# lab2_samarin_boost.net
KiCad netlist of a schematic drawn in Altium Designer
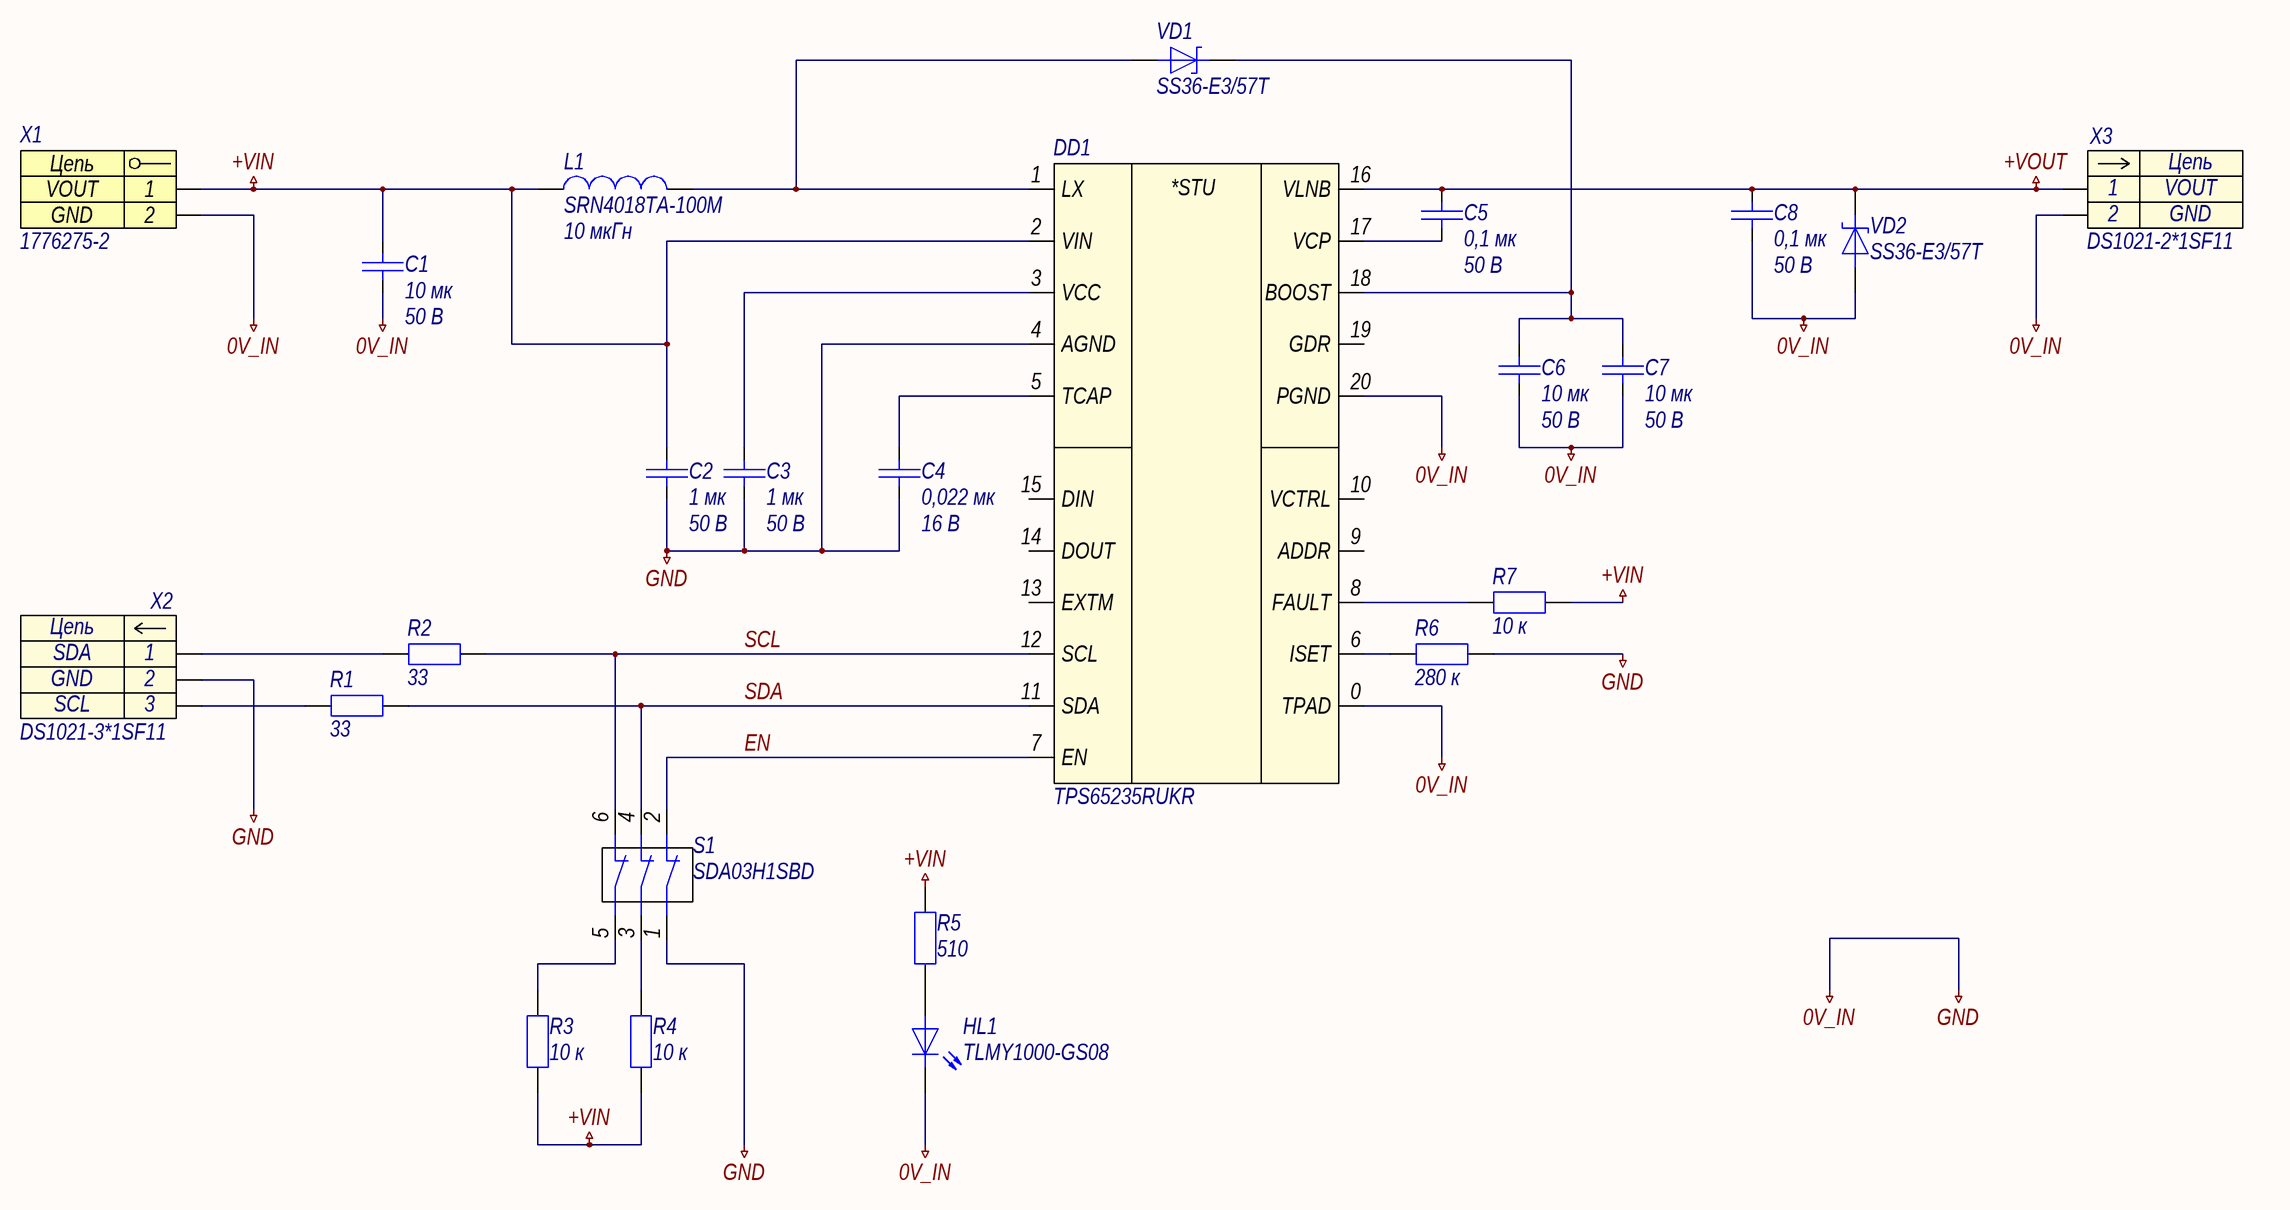
[diagram p0: lab2_samarin_boost.SchDoc]

(export (version "E")
  (design (tool "Eeschema 10.0.6"))
  (components
    (comp (ref "C1")
      (value "10 мк")
      (footprint "C1206")
      (description "=Описание")
      (fields (field (name "НАПРЯЖЕНИЕ") "50 В"))
      (libsource (lib "Database_Students") (part "C-NONPOLAR"))
    )
    (comp (ref "C2")
      (value "1 мк")
      (footprint "C0603")
      (description "=Описание")
      (fields (field (name "НАПРЯЖЕНИЕ") "50 В"))
      (libsource (lib "Database_Students") (part "C-NONPOLAR"))
    )
    (comp (ref "C3")
      (value "1 мк")
      (footprint "C0603")
      (description "=Описание")
      (fields (field (name "НАПРЯЖЕНИЕ") "50 В"))
      (libsource (lib "Database_Students") (part "C-NONPOLAR"))
    )
    (comp (ref "C4")
      (value "0,022 мк")
      (footprint "C0201")
      (description "=Описание")
      (fields (field (name "НАПРЯЖЕНИЕ") "16 В"))
      (libsource (lib "Database_Students") (part "C-NONPOLAR"))
    )
    (comp (ref "C5")
      (value "0,1 мк")
      (footprint "C0603")
      (description "=Описание")
      (fields (field (name "НАПРЯЖЕНИЕ") "50 В"))
      (libsource (lib "Database_Students") (part "C-NONPOLAR"))
    )
    (comp (ref "C6")
      (value "10 мк")
      (footprint "C1206")
      (description "=Описание")
      (fields (field (name "НАПРЯЖЕНИЕ") "50 В"))
      (libsource (lib "Database_Students") (part "C-NONPOLAR"))
    )
    (comp (ref "C7")
      (value "10 мк")
      (footprint "C1206")
      (description "=Описание")
      (fields (field (name "НАПРЯЖЕНИЕ") "50 В"))
      (libsource (lib "Database_Students") (part "C-NONPOLAR"))
    )
    (comp (ref "C8")
      (value "0,1 мк")
      (footprint "C0603")
      (description "=Описание")
      (fields (field (name "НАПРЯЖЕНИЕ") "50 В"))
      (libsource (lib "Database_Students") (part "C-NONPOLAR"))
    )
    (comp (ref "DD1")
      (value "TPS65235RUKR")
      (footprint "QFN-20")
      (description "=Описание")
      (libsource (lib "Database_Students") (part "TPS65235RUKR"))
    )
    (comp (ref "HL1")
      (value "TLMY1000-GS08")
      (footprint "HL0603")
      (description "=Описание")
      (libsource (lib "Database_Students") (part "HL-COMMON"))
    )
    (comp (ref "L1")
      (value "SRN4018TA-100M")
      (footprint "SRN-2-400X400X180")
      (description "=Описание")
      (fields (field (name "ИНДУКТИВНОСТЬ") "10 мкГн"))
      (libsource (lib "Database_Students") (part "INDUCTOR-COMMON"))
    )
    (comp (ref "R1")
      (value "33")
      (footprint "R0603")
      (description "=Описание")
      (libsource (lib "Database_Students") (part "R-COMMON"))
    )
    (comp (ref "R2")
      (value "33")
      (footprint "R0603")
      (description "=Описание")
      (libsource (lib "Database_Students") (part "R-COMMON"))
    )
    (comp (ref "R3")
      (value "10 к")
      (footprint "R0603")
      (description "=Описание")
      (libsource (lib "Database_Students") (part "R-COMMON"))
    )
    (comp (ref "R4")
      (value "10 к")
      (footprint "R0603")
      (description "=Описание")
      (libsource (lib "Database_Students") (part "R-COMMON"))
    )
    (comp (ref "R5")
      (value "510")
      (footprint "R0603")
      (description "=Описание")
      (libsource (lib "Database_Students") (part "R-COMMON"))
    )
    (comp (ref "R6")
      (value "280 к")
      (footprint "R0603")
      (description "=Описание")
      (libsource (lib "Database_Students") (part "R-COMMON"))
    )
    (comp (ref "R7")
      (value "10 к")
      (footprint "R0603")
      (description "=Описание")
      (libsource (lib "Database_Students") (part "R-COMMON"))
    )
    (comp (ref "S1")
      (value "SDA03H1SBD")
      (footprint "DIP-SWITCH-03")
      (description "=Описание")
      (libsource (lib "Database_Students") (part "SWITCH-03"))
    )
    (comp (ref "VD1")
      (value "SS36-E3/57T")
      (footprint "DO-214AB")
      (description "=Описание")
      (libsource (lib "Database_Students") (part "DIODE-SCHOTTKY"))
    )
    (comp (ref "VD2")
      (value "SS36-E3/57T")
      (footprint "DO-214AB")
      (description "=Описание")
      (libsource (lib "Database_Students") (part "DIODE-SCHOTTKY"))
    )
    (comp (ref "X1")
      (value "1776275-2")
      (footprint "1776275-2")
      (description "=Описание")
      (libsource (lib "Database_Students") (part "HEADER-2-TRM"))
    )
    (comp (ref "X2")
      (value "DS1021-3*1SF11")
      (footprint "pls-2,54-3-tht-v:pls-2,54-3")
      (libsource (lib "header-3_plg") (part "HEADER-3_PLG"))
    )
    (comp (ref "X3")
      (value "DS1021-2*1SF11")
      (footprint "pls-2,54-2-tht-v:pls-2,54")
      (libsource (lib "header-2_plg") (part "HEADER-2_PLG"))
    )
  )
  (nets
    (net (code "1") (name "+VIN") (class "Default")
      (node (ref "C1") (pin "1") (pinfunction "1_1") (pintype "passive"))
      (node (ref "C2") (pin "1") (pinfunction "1_1") (pintype "passive"))
      (node (ref "DD1") (pin "2") (pinfunction "VIN_2") (pintype "passive"))
      (node (ref "L1") (pin "1") (pinfunction "1_1") (pintype "passive"))
      (node (ref "R3") (pin "1") (pinfunction "1_1") (pintype "passive"))
      (node (ref "R4") (pin "1") (pinfunction "1_1") (pintype "passive"))
      (node (ref "R5") (pin "2") (pinfunction "2_2") (pintype "passive"))
      (node (ref "R7") (pin "2") (pinfunction "2_2") (pintype "passive"))
      (node (ref "X1") (pin "1") (pinfunction "1_1") (pintype "passive"))
    )
    (net (code "2") (name "+VOUT") (class "Default")
      (node (ref "C5") (pin "1") (pinfunction "1_1") (pintype "passive"))
      (node (ref "C8") (pin "1") (pinfunction "1_1") (pintype "passive"))
      (node (ref "DD1") (pin "16") (pinfunction "VLNB_16") (pintype "passive"))
      (node (ref "VD2") (pin "1") (pinfunction "1_1") (pintype "passive"))
      (node (ref "X3") (pin "1") (pinfunction "1_1") (pintype "passive"))
    )
    (net (code "3") (name "/EN") (class "Default")
      (node (ref "DD1") (pin "7") (pinfunction "EN_7") (pintype "passive"))
      (node (ref "S1") (pin "2") (pinfunction "2_2") (pintype "passive"))
    )
    (net (code "4") (name "/SCL") (class "Default")
      (node (ref "DD1") (pin "12") (pinfunction "SCL_12") (pintype "passive"))
      (node (ref "R2") (pin "2") (pinfunction "2_2") (pintype "passive"))
      (node (ref "S1") (pin "6") (pinfunction "6_6") (pintype "passive"))
    )
    (net (code "5") (name "/SDA") (class "Default")
      (node (ref "DD1") (pin "11") (pinfunction "SDA_11") (pintype "passive"))
      (node (ref "R1") (pin "2") (pinfunction "2_2") (pintype "passive"))
      (node (ref "S1") (pin "4") (pinfunction "4_4") (pintype "passive"))
    )
    (net (code "6") (name "0V_IN") (class "Default")
      (node (ref "C1") (pin "2") (pinfunction "2_2") (pintype "passive"))
      (node (ref "C2") (pin "2") (pinfunction "2_2") (pintype "passive"))
      (node (ref "C3") (pin "2") (pinfunction "2_2") (pintype "passive"))
      (node (ref "C4") (pin "2") (pinfunction "2_2") (pintype "passive"))
      (node (ref "C6") (pin "2") (pinfunction "2_2") (pintype "passive"))
      (node (ref "C7") (pin "2") (pinfunction "2_2") (pintype "passive"))
      (node (ref "C8") (pin "2") (pinfunction "2_2") (pintype "passive"))
      (node (ref "DD1") (pin "0") (pinfunction "TPAD_0") (pintype "passive"))
      (node (ref "DD1") (pin "20") (pinfunction "PGND_20") (pintype "passive"))
      (node (ref "DD1") (pin "4") (pinfunction "AGND_4") (pintype "passive"))
      (node (ref "HL1") (pin "1") (pinfunction "1_1") (pintype "passive"))
      (node (ref "R6") (pin "2") (pinfunction "2_2") (pintype "passive"))
      (node (ref "S1") (pin "1") (pinfunction "1_1") (pintype "passive"))
      (node (ref "VD2") (pin "2") (pinfunction "2_2") (pintype "passive"))
      (node (ref "X1") (pin "2") (pinfunction "2_2") (pintype "passive"))
      (node (ref "X2") (pin "2") (pinfunction "2_2") (pintype "passive"))
      (node (ref "X3") (pin "2") (pinfunction "2_2") (pintype "passive"))
    )
    (net (code "7") (name "Net-(DD1-BOOST)") (class "Default")
      (node (ref "C6") (pin "1") (pinfunction "1_1") (pintype "passive"))
      (node (ref "C7") (pin "1") (pinfunction "1_1") (pintype "passive"))
      (node (ref "DD1") (pin "18") (pinfunction "BOOST_18") (pintype "passive"))
      (node (ref "VD1") (pin "1") (pinfunction "1_1") (pintype "passive"))
    )
    (net (code "8") (name "Net-(DD1-FAULT)") (class "Default")
      (node (ref "DD1") (pin "8") (pinfunction "FAULT_8") (pintype "passive"))
      (node (ref "R7") (pin "1") (pinfunction "1_1") (pintype "passive"))
    )
    (net (code "9") (name "Net-(DD1-ISET)") (class "Default")
      (node (ref "DD1") (pin "6") (pinfunction "ISET_6") (pintype "passive"))
      (node (ref "R6") (pin "1") (pinfunction "1_1") (pintype "passive"))
    )
    (net (code "10") (name "Net-(DD1-LX)") (class "Default")
      (node (ref "DD1") (pin "1") (pinfunction "LX_1") (pintype "passive"))
      (node (ref "L1") (pin "2") (pinfunction "2_2") (pintype "passive"))
      (node (ref "VD1") (pin "2") (pinfunction "2_2") (pintype "passive"))
    )
    (net (code "11") (name "Net-(DD1-TCAP)") (class "Default")
      (node (ref "C4") (pin "1") (pinfunction "1_1") (pintype "passive"))
      (node (ref "DD1") (pin "5") (pinfunction "TCAP_5") (pintype "passive"))
    )
    (net (code "12") (name "Net-(DD1-VCC)") (class "Default")
      (node (ref "C3") (pin "1") (pinfunction "1_1") (pintype "passive"))
      (node (ref "DD1") (pin "3") (pinfunction "VCC_3") (pintype "passive"))
    )
    (net (code "13") (name "Net-(DD1-VCP)") (class "Default")
      (node (ref "C5") (pin "2") (pinfunction "2_2") (pintype "passive"))
      (node (ref "DD1") (pin "17") (pinfunction "VCP_17") (pintype "passive"))
    )
    (net (code "14") (name "Net-(HL1-Pad2)") (class "Default")
      (node (ref "HL1") (pin "2") (pinfunction "2_2") (pintype "passive"))
      (node (ref "R5") (pin "1") (pinfunction "1_1") (pintype "passive"))
    )
    (net (code "15") (name "Net-(R1-Pad1)") (class "Default")
      (node (ref "R1") (pin "1") (pinfunction "1_1") (pintype "passive"))
      (node (ref "X2") (pin "3") (pinfunction "3_3") (pintype "passive"))
    )
    (net (code "16") (name "Net-(R2-Pad1)") (class "Default")
      (node (ref "R2") (pin "1") (pinfunction "1_1") (pintype "passive"))
      (node (ref "X2") (pin "1") (pinfunction "1_1") (pintype "passive"))
    )
    (net (code "17") (name "Net-(R3-Pad2)") (class "Default")
      (node (ref "R3") (pin "2") (pinfunction "2_2") (pintype "passive"))
      (node (ref "S1") (pin "5") (pinfunction "5_5") (pintype "passive"))
    )
    (net (code "18") (name "Net-(R4-Pad2)") (class "Default")
      (node (ref "R4") (pin "2") (pinfunction "2_2") (pintype "passive"))
      (node (ref "S1") (pin "3") (pinfunction "3_3") (pintype "passive"))
    )
    (net (code "19") (name "unconnected-(DD1-ADDR-Pad9)") (class "Default")
      (node (ref "DD1") (pin "9") (pinfunction "ADDR_9") (pintype "passive"))
    )
    (net (code "20") (name "unconnected-(DD1-DIN-Pad15)") (class "Default")
      (node (ref "DD1") (pin "15") (pinfunction "DIN_15") (pintype "passive"))
    )
    (net (code "21") (name "unconnected-(DD1-DOUT-Pad14)") (class "Default")
      (node (ref "DD1") (pin "14") (pinfunction "DOUT_14") (pintype "passive"))
    )
    (net (code "22") (name "unconnected-(DD1-EXTM-Pad13)") (class "Default")
      (node (ref "DD1") (pin "13") (pinfunction "EXTM_13") (pintype "passive"))
    )
    (net (code "23") (name "unconnected-(DD1-GDR-Pad19)") (class "Default")
      (node (ref "DD1") (pin "19") (pinfunction "GDR_19") (pintype "passive"))
    )
    (net (code "24") (name "unconnected-(DD1-VCTRL-Pad10)") (class "Default")
      (node (ref "DD1") (pin "10") (pinfunction "VCTRL_10") (pintype "passive"))
    )
  )
)
